# IOControl.net
KiCad netlist of a schematic drawn in Altium Designer
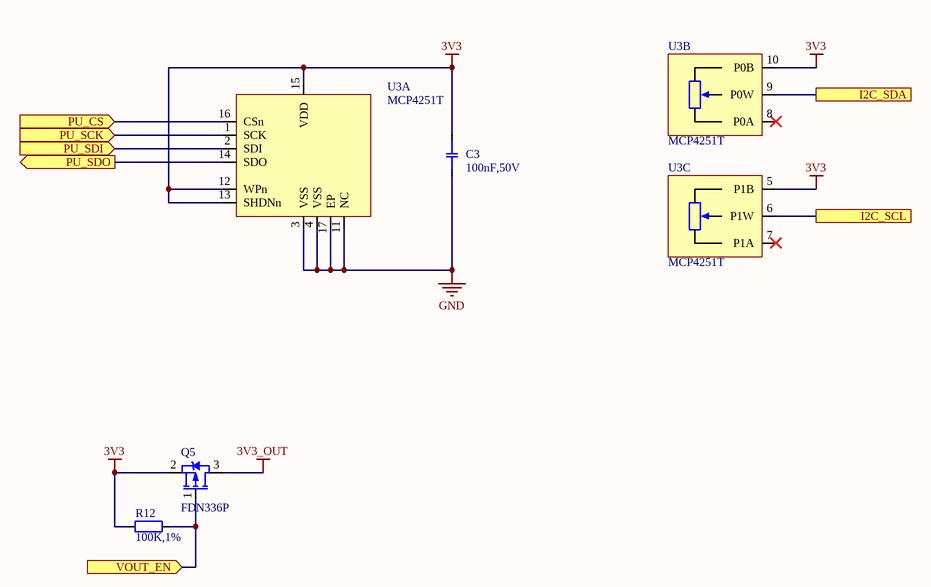
[diagram p0: IOControl.SchDoc]

(export (version "E")
  (design (tool "Eeschema 10.0.6"))
  (components
    (comp (ref "C3")
      (value "100nF,50V")
      (footprint "CAPC1608X09N_0603")
      (description "CAP CER 0.1UF 50V 10% X7R 0603")
      (fields (field (name "MANUFACTURER") "Kemet") (field (name "TOLERANCE") "10%"))
      (libsource (lib "library") (part "CAP-NP_1"))
    )
    (comp (ref "Q5")
      (value "FDN336P")
      (footprint "SOT95P230X110-3N_SOT23")
      (description "MOSFET P-Channel")
      (fields (field (name "MANUFACTURER") "Fairchild Semiconductor"))
      (libsource (lib "library") (part "MOSFET-P_1"))
    )
    (comp (ref "R12")
      (value "100K,1%")
      (footprint "RESC1608X06N_0603")
      (description "RES 100K OHM 1/10W 1% 0603 SMD")
      (fields (field (name "MANUFACTURER") "Yageo") (field (name "POWER") "0.1W"))
      (libsource (lib "library") (part "RESISTOR_1"))
    )
    (comp (ref "U3")
      (value "MCP4251T")
      (footprint "QFN65P400X400X90_HS-16N")
      (description "IC DGTL POT 10KOHM 257TAP 16QFN")
      (fields
        (field (name "MANUFACTURER") "Microchip Technology")
        (field (name "MANUFACTURER PART NUMBER") "MCP4251T-103E/ML")
      )
      (libsource (lib "library") (part "MCP4241T-103E"))
    )
  )
  (nets
    (net (code "1") (name "/I2C_SCL") (class "Default")
      (node (ref "U3") (pin "6") (pinfunction "P1W_6") (pintype "passive"))
    )
    (net (code "2") (name "/I2C_SDA") (class "Default")
      (node (ref "U3") (pin "9") (pinfunction "P0W_9") (pintype "passive"))
    )
    (net (code "3") (name "/PU_CS") (class "Default")
      (node (ref "U3") (pin "16") (pinfunction "CSn_16") (pintype "passive"))
    )
    (net (code "4") (name "/PU_SCK") (class "Default")
      (node (ref "U3") (pin "1") (pinfunction "SCK_1") (pintype "passive"))
    )
    (net (code "5") (name "/PU_SDI") (class "Default")
      (node (ref "U3") (pin "2") (pinfunction "SDI_2") (pintype "passive"))
    )
    (net (code "6") (name "/PU_SDO") (class "Default")
      (node (ref "U3") (pin "14") (pinfunction "SDO_14") (pintype "passive"))
    )
    (net (code "7") (name "/VOUT_EN") (class "Default")
      (node (ref "Q5") (pin "1") (pinfunction "G_1") (pintype "passive"))
      (node (ref "R12") (pin "1") (pinfunction "1_1") (pintype "passive"))
    )
    (net (code "8") (name "3V3") (class "Default")
      (node (ref "C3") (pin "2") (pinfunction "2_2") (pintype "passive"))
      (node (ref "Q5") (pin "2") (pinfunction "S_2") (pintype "passive"))
      (node (ref "R12") (pin "2") (pinfunction "2_2") (pintype "passive"))
      (node (ref "U3") (pin "10") (pinfunction "P0B_10") (pintype "passive"))
      (node (ref "U3") (pin "12") (pinfunction "WPn_12") (pintype "passive"))
      (node (ref "U3") (pin "13") (pinfunction "SHDNn_13") (pintype "passive"))
      (node (ref "U3") (pin "15") (pinfunction "VDD_15") (pintype "passive"))
      (node (ref "U3") (pin "5") (pinfunction "P1B_5") (pintype "passive"))
    )
    (net (code "9") (name "3V3_OUT") (class "Default")
      (node (ref "Q5") (pin "3") (pinfunction "D_3") (pintype "passive"))
    )
    (net (code "10") (name "GND") (class "Default")
      (node (ref "C3") (pin "1") (pinfunction "1_1") (pintype "passive"))
      (node (ref "U3") (pin "11") (pinfunction "NC_11") (pintype "passive"))
      (node (ref "U3") (pin "17") (pinfunction "EP_17") (pintype "passive"))
      (node (ref "U3") (pin "3") (pinfunction "VSS_3") (pintype "passive"))
      (node (ref "U3") (pin "4") (pinfunction "VSS_4") (pintype "passive"))
    )
    (net (code "11") (name "unconnected-(U3B-P0A-Pad8)") (class "Default")
      (node (ref "U3") (pin "8") (pinfunction "P0A_8") (pintype "passive+no_connect"))
    )
    (net (code "12") (name "unconnected-(U3C-P1A-Pad7)") (class "Default")
      (node (ref "U3") (pin "7") (pinfunction "P1A_7") (pintype "passive+no_connect"))
    )
  )
)
